# TS04.net
KiCad netlist of a schematic drawn in Altium Designer
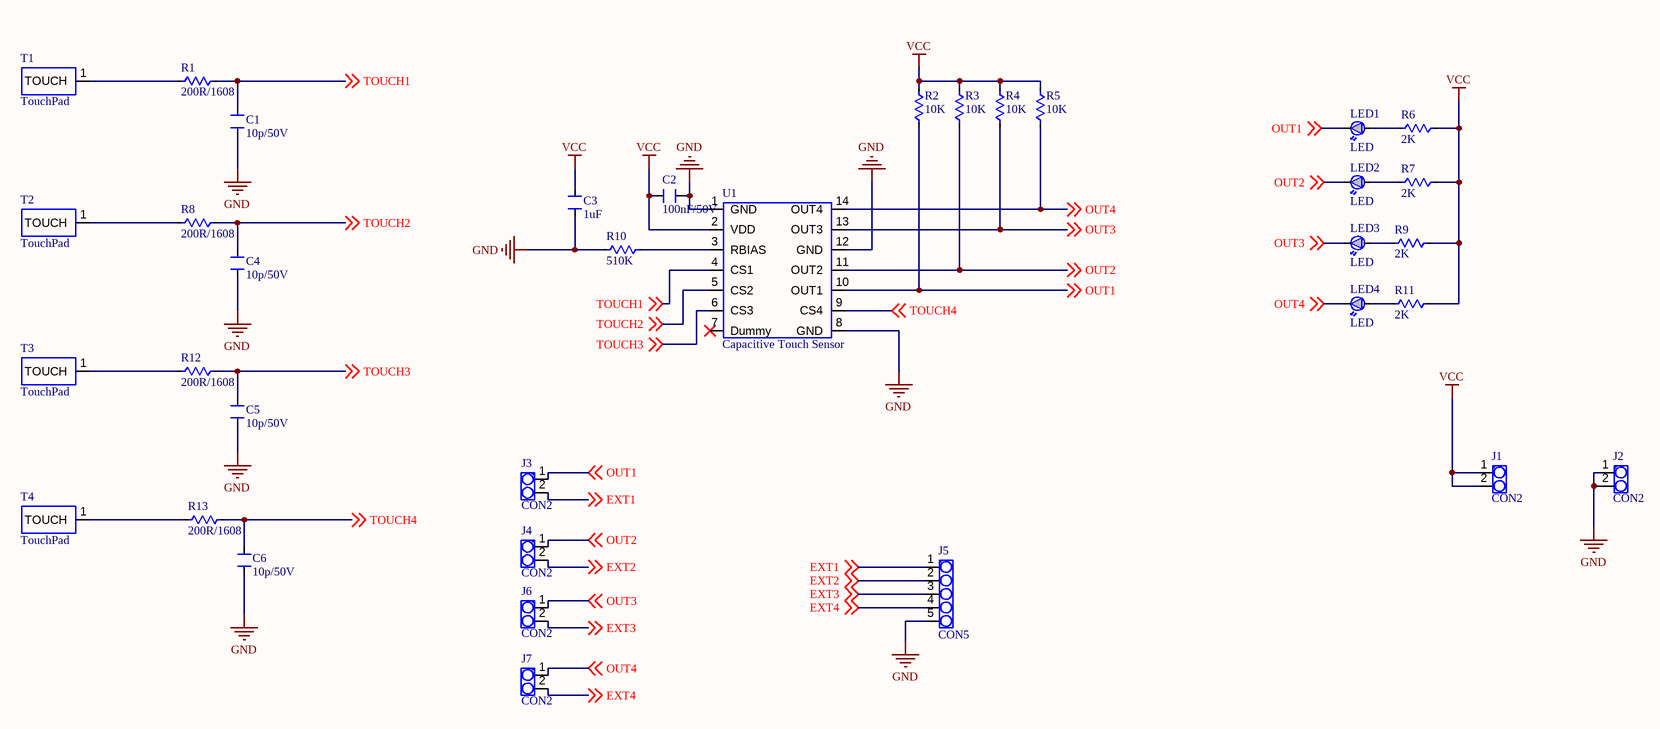
[diagram p0: TS04.SchDoc]

(export (version "E")
  (design (tool "Eeschema 10.0.6"))
  (components
    (comp (ref "C1")
      (value "10p/50V")
      (footprint "C1608")
      (description "SMD TYPE CAPACITOR")
      (libsource (lib "PASSIVE") (part "CHIP_CAP"))
    )
    (comp (ref "C2")
      (value "100nF/50V")
      (footprint "C1608")
      (description "SMD TYPE CAPACITOR")
      (libsource (lib "PASSIVE") (part "CHIP_CAP"))
    )
    (comp (ref "C3")
      (value "1uF")
      (footprint "C1608")
      (description "SMD TYPE CAPACITOR")
      (libsource (lib "PASSIVE") (part "CHIP_CAP"))
    )
    (comp (ref "C4")
      (value "10p/50V")
      (footprint "C1608")
      (description "SMD TYPE CAPACITOR")
      (libsource (lib "PASSIVE") (part "CHIP_CAP"))
    )
    (comp (ref "C5")
      (value "10p/50V")
      (footprint "C1608")
      (description "SMD TYPE CAPACITOR")
      (libsource (lib "PASSIVE") (part "CHIP_CAP"))
    )
    (comp (ref "C6")
      (value "10p/50V")
      (footprint "C1608")
      (description "SMD TYPE CAPACITOR")
      (libsource (lib "PASSIVE") (part "CHIP_CAP"))
    )
    (comp (ref "J1") (value "CON2") (footprint "HEADER_V254_1X2") (libsource (lib "CONNECTOR") (part "CON2")))
    (comp (ref "J2") (value "CON2") (footprint "HEADER_V254_1X2") (libsource (lib "CONNECTOR") (part "CON2")))
    (comp (ref "J3") (value "CON2") (footprint "HEADER_V254_1X2") (libsource (lib "") (part "CON2_1")))
    (comp (ref "J4") (value "CON2") (footprint "HEADER_V254_1X2") (libsource (lib "") (part "CON2_1")))
    (comp (ref "J5") (value "CON5") (footprint "HEADER_V254_1X5") (libsource (lib "CONNECTOR") (part "CON5")))
    (comp (ref "J6") (value "CON2") (footprint "HEADER_V254_1X2") (libsource (lib "") (part "CON2_1")))
    (comp (ref "J7") (value "CON2") (footprint "HEADER_V254_1X2") (libsource (lib "") (part "CON2_1")))
    (comp (ref "LED1") (value "LED") (footprint "LED/SMD1608") (libsource (lib "DISCRETE") (part "LED")))
    (comp (ref "LED2") (value "LED") (footprint "LED/SMD1608") (libsource (lib "DISCRETE") (part "LED")))
    (comp (ref "LED3") (value "LED") (footprint "LED/SMD1608") (libsource (lib "DISCRETE") (part "LED")))
    (comp (ref "LED4") (value "LED") (footprint "LED/SMD1608") (libsource (lib "DISCRETE") (part "LED")))
    (comp (ref "R1")
      (value "200R/1608")
      (footprint "R1608")
      (description "SMD TYPE RESISTOR")
      (libsource (lib "PASSIVE") (part "CHIP_RES"))
    )
    (comp (ref "R2")
      (value "10K")
      (footprint "R1608")
      (description "SMD TYPE RESISTOR")
      (libsource (lib "PASSIVE") (part "CHIP_RES"))
    )
    (comp (ref "R3")
      (value "10K")
      (footprint "R1608")
      (description "SMD TYPE RESISTOR")
      (libsource (lib "PASSIVE") (part "CHIP_RES"))
    )
    (comp (ref "R4")
      (value "10K")
      (footprint "R1608")
      (description "SMD TYPE RESISTOR")
      (libsource (lib "PASSIVE") (part "CHIP_RES"))
    )
    (comp (ref "R5")
      (value "10K")
      (footprint "R1608")
      (description "SMD TYPE RESISTOR")
      (libsource (lib "PASSIVE") (part "CHIP_RES"))
    )
    (comp (ref "R6")
      (value "2K")
      (footprint "R1608")
      (description "SMD TYPE RESISTOR")
      (libsource (lib "PASSIVE") (part "CHIP_RES"))
    )
    (comp (ref "R7")
      (value "2K")
      (footprint "R1608")
      (description "SMD TYPE RESISTOR")
      (libsource (lib "PASSIVE") (part "CHIP_RES"))
    )
    (comp (ref "R8")
      (value "200R/1608")
      (footprint "R1608")
      (description "SMD TYPE RESISTOR")
      (libsource (lib "PASSIVE") (part "CHIP_RES"))
    )
    (comp (ref "R9")
      (value "2K")
      (footprint "R1608")
      (description "SMD TYPE RESISTOR")
      (libsource (lib "PASSIVE") (part "CHIP_RES"))
    )
    (comp (ref "R10")
      (value "510K")
      (footprint "R1608")
      (description "SMD TYPE RESISTOR")
      (libsource (lib "PASSIVE") (part "CHIP_RES"))
    )
    (comp (ref "R11")
      (value "2K")
      (footprint "R1608")
      (description "SMD TYPE RESISTOR")
      (libsource (lib "PASSIVE") (part "CHIP_RES"))
    )
    (comp (ref "R12")
      (value "200R/1608")
      (footprint "R1608")
      (description "SMD TYPE RESISTOR")
      (libsource (lib "PASSIVE") (part "CHIP_RES"))
    )
    (comp (ref "R13")
      (value "200R/1608")
      (footprint "R1608")
      (description "SMD TYPE RESISTOR")
      (libsource (lib "PASSIVE") (part "CHIP_RES"))
    )
    (comp (ref "T1") (value "TouchPad") (footprint "TOUCHPAD") (libsource (lib "DISCRETE") (part "TouchPad")))
    (comp (ref "T2") (value "TouchPad") (footprint "TOUCHPAD") (libsource (lib "DISCRETE") (part "TouchPad")))
    (comp (ref "T3") (value "TouchPad") (footprint "TOUCHPAD") (libsource (lib "DISCRETE") (part "TouchPad")))
    (comp (ref "T4") (value "TouchPad") (footprint "TOUCHPAD") (libsource (lib "DISCRETE") (part "TouchPad")))
    (comp (ref "U1")
      (value "Capacitive Touch Sensor")
      (footprint "TS04_SOP14")
      (description "Capacitive Touch Sensor from AD Semiconductor SOP14 Type")
      (libsource (lib "IC") (part "TS04_SOP14"))
    )
  )
  (nets
    (net (code "1") (name "EXT1") (class "Default")
      (node (ref "J3") (pin "2") (pintype "passive"))
      (node (ref "J5") (pin "1") (pintype "passive"))
    )
    (net (code "2") (name "EXT2") (class "Default")
      (node (ref "J4") (pin "2") (pintype "passive"))
      (node (ref "J5") (pin "2") (pintype "passive"))
    )
    (net (code "3") (name "EXT3") (class "Default")
      (node (ref "J5") (pin "3") (pintype "passive"))
      (node (ref "J6") (pin "2") (pintype "passive"))
    )
    (net (code "4") (name "EXT4") (class "Default")
      (node (ref "J5") (pin "4") (pintype "passive"))
      (node (ref "J7") (pin "2") (pintype "passive"))
    )
    (net (code "5") (name "GND") (class "Default")
      (node (ref "C1") (pin "2") (pintype "passive"))
      (node (ref "C2") (pin "2") (pintype "passive"))
      (node (ref "C3") (pin "1") (pintype "passive"))
      (node (ref "C4") (pin "2") (pintype "passive"))
      (node (ref "C5") (pin "2") (pintype "passive"))
      (node (ref "C6") (pin "2") (pintype "passive"))
      (node (ref "J2") (pin "1") (pintype "passive"))
      (node (ref "J2") (pin "2") (pintype "passive"))
      (node (ref "J5") (pin "5") (pintype "passive"))
      (node (ref "R10") (pin "1") (pintype "passive"))
      (node (ref "U1") (pin "1") (pinfunction "GND_1") (pintype "passive"))
      (node (ref "U1") (pin "12") (pinfunction "GND_12") (pintype "passive"))
      (node (ref "U1") (pin "8") (pinfunction "GND_8") (pintype "passive"))
    )
    (net (code "6") (name "Net-(LED1-A)") (class "Default")
      (node (ref "LED1") (pin "2") (pinfunction "A_2") (pintype "passive"))
      (node (ref "R6") (pin "2") (pintype "passive"))
    )
    (net (code "7") (name "Net-(LED2-A)") (class "Default")
      (node (ref "LED2") (pin "2") (pinfunction "A_2") (pintype "passive"))
      (node (ref "R7") (pin "2") (pintype "passive"))
    )
    (net (code "8") (name "Net-(LED3-A)") (class "Default")
      (node (ref "LED3") (pin "2") (pinfunction "A_2") (pintype "passive"))
      (node (ref "R9") (pin "2") (pintype "passive"))
    )
    (net (code "9") (name "Net-(LED4-A)") (class "Default")
      (node (ref "LED4") (pin "2") (pinfunction "A_2") (pintype "passive"))
      (node (ref "R11") (pin "2") (pintype "passive"))
    )
    (net (code "10") (name "Net-(T1-TOUCH)") (class "Default")
      (node (ref "R1") (pin "1") (pintype "passive"))
      (node (ref "T1") (pin "1") (pinfunction "TOUCH_1") (pintype "passive"))
    )
    (net (code "11") (name "Net-(T2-TOUCH)") (class "Default")
      (node (ref "R8") (pin "1") (pintype "passive"))
      (node (ref "T2") (pin "1") (pinfunction "TOUCH_1") (pintype "passive"))
    )
    (net (code "12") (name "Net-(T3-TOUCH)") (class "Default")
      (node (ref "R12") (pin "1") (pintype "passive"))
      (node (ref "T3") (pin "1") (pinfunction "TOUCH_1") (pintype "passive"))
    )
    (net (code "13") (name "Net-(T4-TOUCH)") (class "Default")
      (node (ref "R13") (pin "1") (pintype "passive"))
      (node (ref "T4") (pin "1") (pinfunction "TOUCH_1") (pintype "passive"))
    )
    (net (code "14") (name "Net-(U1-RBIAS)") (class "Default")
      (node (ref "R10") (pin "2") (pintype "passive"))
      (node (ref "U1") (pin "3") (pinfunction "RBIAS_3") (pintype "passive"))
    )
    (net (code "15") (name "OUT1") (class "Default")
      (node (ref "J3") (pin "1") (pintype "passive"))
      (node (ref "LED1") (pin "1") (pinfunction "C_1") (pintype "passive"))
      (node (ref "R2") (pin "1") (pintype "passive"))
      (node (ref "U1") (pin "10") (pinfunction "OUT1_10") (pintype "passive"))
    )
    (net (code "16") (name "OUT2") (class "Default")
      (node (ref "J4") (pin "1") (pintype "passive"))
      (node (ref "LED2") (pin "1") (pinfunction "C_1") (pintype "passive"))
      (node (ref "R3") (pin "1") (pintype "passive"))
      (node (ref "U1") (pin "11") (pinfunction "OUT2_11") (pintype "passive"))
    )
    (net (code "17") (name "OUT3") (class "Default")
      (node (ref "J6") (pin "1") (pintype "passive"))
      (node (ref "LED3") (pin "1") (pinfunction "C_1") (pintype "passive"))
      (node (ref "R4") (pin "1") (pintype "passive"))
      (node (ref "U1") (pin "13") (pinfunction "OUT3_13") (pintype "passive"))
    )
    (net (code "18") (name "OUT4") (class "Default")
      (node (ref "J7") (pin "1") (pintype "passive"))
      (node (ref "LED4") (pin "1") (pinfunction "C_1") (pintype "passive"))
      (node (ref "R5") (pin "1") (pintype "passive"))
      (node (ref "U1") (pin "14") (pinfunction "OUT4_14") (pintype "passive"))
    )
    (net (code "19") (name "TOUCH1") (class "Default")
      (node (ref "C1") (pin "1") (pintype "passive"))
      (node (ref "R1") (pin "2") (pintype "passive"))
      (node (ref "U1") (pin "4") (pinfunction "CS1_4") (pintype "passive"))
    )
    (net (code "20") (name "TOUCH2") (class "Default")
      (node (ref "C4") (pin "1") (pintype "passive"))
      (node (ref "R8") (pin "2") (pintype "passive"))
      (node (ref "U1") (pin "5") (pinfunction "CS2_5") (pintype "passive"))
    )
    (net (code "21") (name "TOUCH3") (class "Default")
      (node (ref "C5") (pin "1") (pintype "passive"))
      (node (ref "R12") (pin "2") (pintype "passive"))
      (node (ref "U1") (pin "6") (pinfunction "CS3_6") (pintype "passive"))
    )
    (net (code "22") (name "TOUCH4") (class "Default")
      (node (ref "C6") (pin "1") (pintype "passive"))
      (node (ref "R13") (pin "2") (pintype "passive"))
      (node (ref "U1") (pin "9") (pinfunction "CS4_9") (pintype "passive"))
    )
    (net (code "23") (name "VCC") (class "Default")
      (node (ref "C2") (pin "1") (pintype "passive"))
      (node (ref "C3") (pin "2") (pintype "passive"))
      (node (ref "J1") (pin "1") (pintype "passive"))
      (node (ref "J1") (pin "2") (pintype "passive"))
      (node (ref "R11") (pin "1") (pintype "passive"))
      (node (ref "R2") (pin "2") (pintype "passive"))
      (node (ref "R3") (pin "2") (pintype "passive"))
      (node (ref "R4") (pin "2") (pintype "passive"))
      (node (ref "R5") (pin "2") (pintype "passive"))
      (node (ref "R6") (pin "1") (pintype "passive"))
      (node (ref "R7") (pin "1") (pintype "passive"))
      (node (ref "R9") (pin "1") (pintype "passive"))
      (node (ref "U1") (pin "2") (pinfunction "VDD_2") (pintype "passive"))
    )
    (net (code "24") (name "unconnected-(U1-Dummy-Pad7)") (class "Default")
      (node (ref "U1") (pin "7") (pinfunction "Dummy_7") (pintype "passive+no_connect"))
    )
  )
)
